# CONNECTOR.net
KiCad netlist of a schematic drawn in Altium Designer
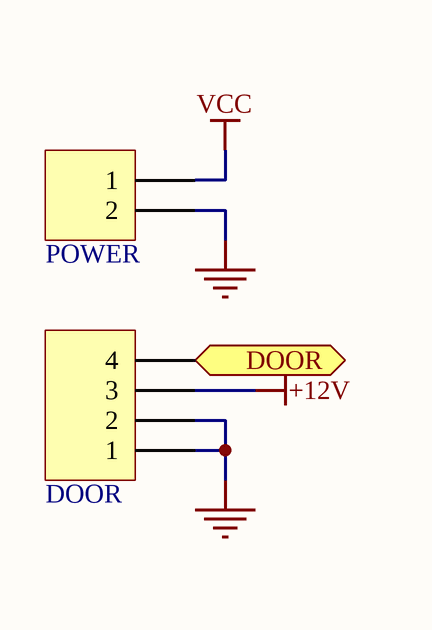
[diagram p0: CONNECTOR.SchDoc]

(export (version "E")
  (design (tool "Eeschema 10.0.6"))
  (components
    (comp (ref "DOOR")
      (value "Header 4")
      (footprint "HX2.54-4")
      (description "Header, 4-Pin")
      (fields (field (name "PUBLISHER") "Altium Limited"))
      (libsource (lib "Peace的集成库") (part "Header 4"))
    )
    (comp (ref "POWER")
      (value "Header 2")
      (footprint "HX2.54-2")
      (description "Header, 2-Pin")
      (fields (field (name "PUBLISHER") "Altium Limited"))
      (libsource (lib "Peace的集成库") (part "Header 2"))
    )
  )
  (nets
    (net (code "1") (name "+12V") (class "Default")
      (node (ref "DOOR") (pin "3") (pinfunction "3_3") (pintype "passive"))
    )
    (net (code "2") (name "/DOOR") (class "Default")
      (node (ref "DOOR") (pin "4") (pinfunction "4_4") (pintype "passive"))
    )
    (net (code "3") (name "GND") (class "Default")
      (node (ref "DOOR") (pin "1") (pinfunction "1_1") (pintype "passive"))
      (node (ref "DOOR") (pin "2") (pinfunction "2_2") (pintype "passive"))
      (node (ref "POWER") (pin "2") (pinfunction "2_2") (pintype "passive"))
    )
    (net (code "4") (name "VCC") (class "Default")
      (node (ref "POWER") (pin "1") (pinfunction "1_1") (pintype "passive"))
    )
  )
)
